# Atmega.net
KiCad netlist of a schematic drawn in Altium Designer
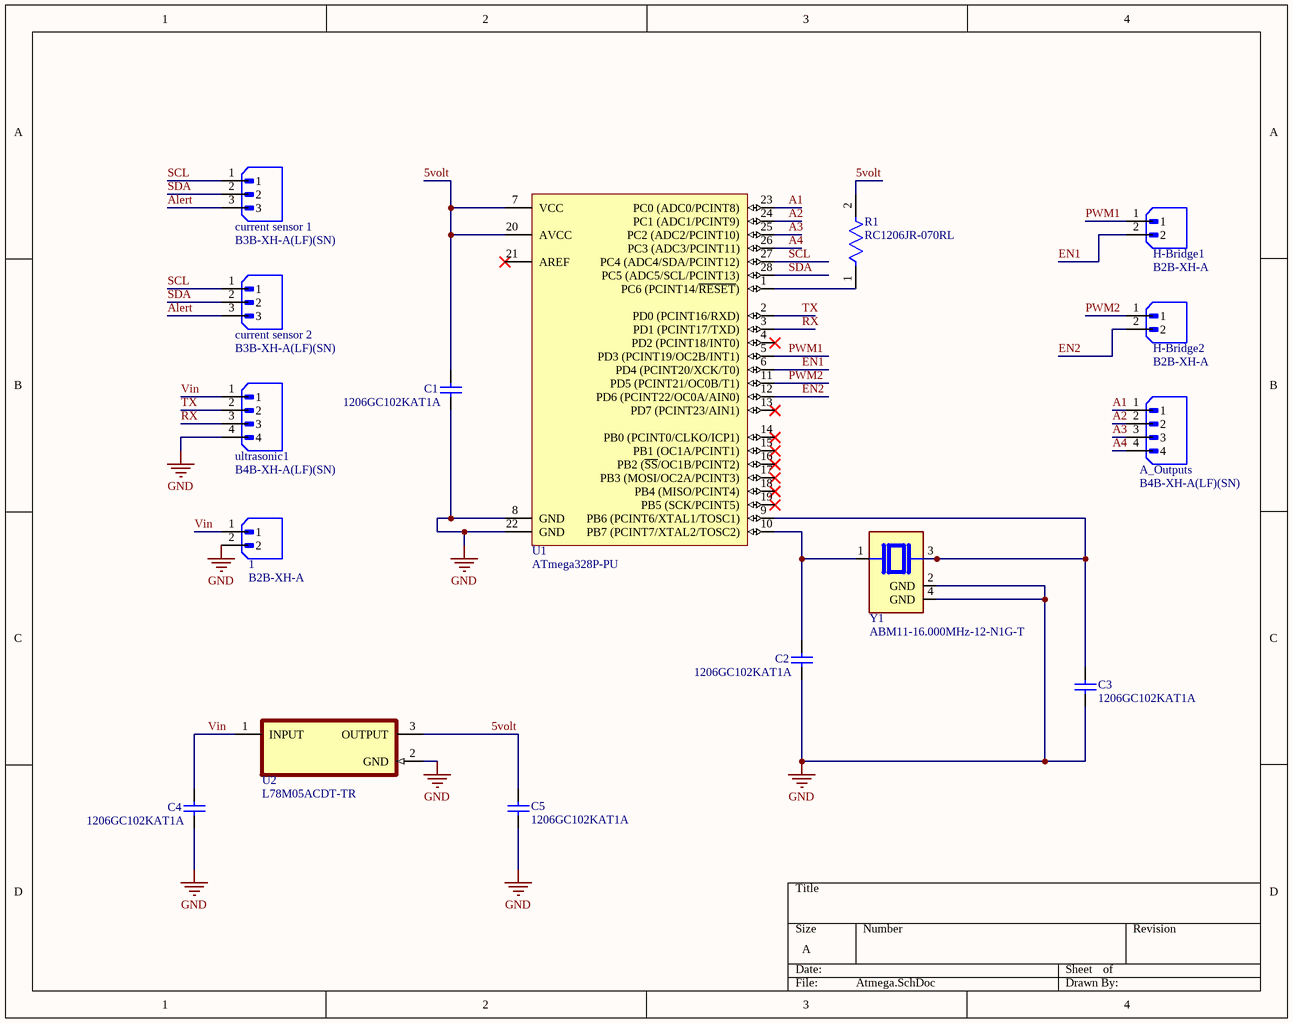
[diagram p0: Atmega.SchDoc]

(export (version "E")
  (design (tool "Eeschema 10.0.6"))
  (components
    (comp (ref "1")
      (value "B2B-XH-A")
      (footprint "JST_B2B-XH-A")
      (fields (field (name "MF") "{'manufacturer': u'JST Sales America Inc.'}"))
      (libsource (lib "B2B-XH-A") (part "B2B-XH-A"))
    )
    (comp (ref "A_Outputs")
      (value "B4B-XH-A(LF)(SN)")
      (footprint "JST_B4B-XH-A(LF)(SN)")
      (description "Connector Header Through Hole 4 position 0.098 (2.50mm)")
      (fields (field (name "MF") "JST Sales"))
      (libsource (lib "B4B-XH-A_LF__SN_") (part "B4B-XH-A(LF)(SN)"))
    )
    (comp (ref "C1")
      (value "1206GC102KAT1A")
      (footprint "AVX-1206-2_L")
      (description "Chip Capacitor, 1 nF, +/- 10%, -55 to 125 degC, 1206 (3216 Metric), RoHS, Tape and Reel")
      (fields (field (name "TOLERANCE") "10%") (field (name "MANUFACTURER") "AVX"))
      (libsource (lib "Altium Content Vault") (part "CAP-NP-2"))
    )
    (comp (ref "C2")
      (value "1206GC102KAT1A")
      (footprint "AVX-1206-2_L")
      (description "Chip Capacitor, 1 nF, +/- 10%, -55 to 125 degC, 1206 (3216 Metric), RoHS, Tape and Reel")
      (fields (field (name "TOLERANCE") "10%") (field (name "MANUFACTURER") "AVX"))
      (libsource (lib "Altium Content Vault") (part "CAP-NP-2"))
    )
    (comp (ref "C3")
      (value "1206GC102KAT1A")
      (footprint "AVX-1206-2_L")
      (description "Chip Capacitor, 1 nF, +/- 10%, -55 to 125 degC, 1206 (3216 Metric), RoHS, Tape and Reel")
      (fields (field (name "TOLERANCE") "10%") (field (name "MANUFACTURER") "AVX"))
      (libsource (lib "Altium Content Vault") (part "CAP-NP-2"))
    )
    (comp (ref "C4")
      (value "1206GC102KAT1A")
      (footprint "AVX-1206-2_L")
      (description "Chip Capacitor, 1 nF, +/- 10%, -55 to 125 degC, 1206 (3216 Metric), RoHS, Tape and Reel")
      (fields (field (name "TOLERANCE") "10%") (field (name "MANUFACTURER") "AVX"))
      (libsource (lib "Altium Content Vault") (part "CAP-NP-2"))
    )
    (comp (ref "C5")
      (value "1206GC102KAT1A")
      (footprint "AVX-1206-2_L")
      (description "Chip Capacitor, 1 nF, +/- 10%, -55 to 125 degC, 1206 (3216 Metric), RoHS, Tape and Reel")
      (fields (field (name "TOLERANCE") "10%") (field (name "MANUFACTURER") "AVX"))
      (libsource (lib "Altium Content Vault") (part "CAP-NP-2"))
    )
    (comp (ref "current sensor 1")
      (value "B3B-XH-A(LF)(SN)")
      (footprint "JST_B3B-XH-A(LF)(SN)")
      (description "Connector Header Through Hole 3 position 0.098 (2.50mm)")
      (fields (field (name "MF") "JST Sales"))
      (libsource (lib "B3B-XH-A_LF__SN_") (part "B3B-XH-A(LF)(SN)"))
    )
    (comp (ref "current sensor 2")
      (value "B3B-XH-A(LF)(SN)")
      (footprint "JST_B3B-XH-A(LF)(SN)")
      (description "Connector Header Through Hole 3 position 0.098 (2.50mm)")
      (fields (field (name "MF") "JST Sales"))
      (libsource (lib "B3B-XH-A_LF__SN_") (part "B3B-XH-A(LF)(SN)"))
    )
    (comp (ref "H-Bridge1")
      (value "B2B-XH-A")
      (footprint "JST_B2B-XH-A")
      (fields (field (name "MF") "{'manufacturer': u'JST Sales America Inc.'}"))
      (libsource (lib "B2B-XH-A") (part "B2B-XH-A"))
    )
    (comp (ref "H-Bridge2")
      (value "B2B-XH-A")
      (footprint "JST_B2B-XH-A")
      (fields (field (name "MF") "{'manufacturer': u'JST Sales America Inc.'}"))
      (libsource (lib "B2B-XH-A") (part "B2B-XH-A"))
    )
    (comp (ref "R1")
      (value "RC1206JR-070RL")
      (footprint "FP-RC1206-MFG")
      (description "RES SMD 0 OHM JUMPER 1/4W 1206")
      (fields
        (field (name "MANUFACTURER") "YAGEO")
        (field (name "OCTOPART") "https://octopart.com/rc1206jr-070rl-yageo-40025601")
      )
      (libsource (lib "Altium Content Vault") (part "1029c3af85768c4190bb7ad29bc67b5"))
    )
    (comp (ref "U1")
      (value "ATmega328P-PU")
      (footprint "28P3")
      (libsource (lib "Altium Content Vault") (part "MC-8B-ATM48-IL28"))
    )
    (comp (ref "U2")
      (value "L78M05ACDT-TR")
      (footprint "DPAK228P972X240-4N")
      (description "Linear Voltage Regulator IC 1 Output 500mA DPAK")
      (fields (field (name "MF") "STMicroelectronics"))
      (libsource (lib "L78M05ACDT-TR") (part "L78M05ACDT-TR"))
    )
    (comp (ref "ultrasonic1")
      (value "B4B-XH-A(LF)(SN)")
      (footprint "JST_B4B-XH-A(LF)(SN)")
      (description "Connector Header Through Hole 4 position 0.098 (2.50mm)")
      (fields (field (name "MF") "JST Sales"))
      (libsource (lib "B4B-XH-A_LF__SN_") (part "B4B-XH-A(LF)(SN)"))
    )
    (comp (ref "Y1")
      (value "ABM11-16.000MHz-12-N1G-T")
      (footprint "XTAL_ABM11-16.000MHz-12-N1G-T")
      (fields (field (name "MF") "{'manufacturer': u'Abracon LLC'}"))
      (libsource (lib "ABM11-16.000MHz-12-N1G-T") (part "ABM11-16.000MHz-12-N1G-T"))
    )
  )
  (nets
    (net (code "1") (name "/5volt") (class "Default")
      (node (ref "C1") (pin "2") (pinfunction "2_2") (pintype "passive"))
      (node (ref "C5") (pin "1") (pinfunction "1_1") (pintype "passive"))
      (node (ref "R1") (pin "2") (pinfunction "2_2") (pintype "passive"))
      (node (ref "U1") (pin "20") (pinfunction "AVCC_20") (pintype "power_in"))
      (node (ref "U1") (pin "7") (pinfunction "VCC_7") (pintype "power_in"))
      (node (ref "U2") (pin "3") (pinfunction "OUTPUT_3") (pintype "power_in"))
    )
    (net (code "2") (name "/A1") (class "Default")
      (node (ref "A_Outputs") (pin "1") (pinfunction "1_1") (pintype "passive"))
      (node (ref "U1") (pin "23") (pinfunction "PC0_(ADC0/PCINT8)_23") (pintype "bidirectional"))
    )
    (net (code "3") (name "/A2") (class "Default")
      (node (ref "A_Outputs") (pin "2") (pinfunction "2_2") (pintype "passive"))
      (node (ref "U1") (pin "24") (pinfunction "PC1_(ADC1/PCINT9)_24") (pintype "bidirectional"))
    )
    (net (code "4") (name "/A3") (class "Default")
      (node (ref "A_Outputs") (pin "3") (pinfunction "3_3") (pintype "passive"))
      (node (ref "U1") (pin "25") (pinfunction "PC2_(ADC2/PCINT10)_25") (pintype "bidirectional"))
    )
    (net (code "5") (name "/A4") (class "Default")
      (node (ref "A_Outputs") (pin "4") (pinfunction "4_4") (pintype "passive"))
      (node (ref "U1") (pin "26") (pinfunction "PC3_(ADC3/PCINT11)_26") (pintype "bidirectional"))
    )
    (net (code "6") (name "/Alert") (class "Default")
      (node (ref "current sensor 1") (pin "3") (pinfunction "3_3") (pintype "passive"))
      (node (ref "current sensor 2") (pin "3") (pinfunction "3_3") (pintype "passive"))
    )
    (net (code "7") (name "/EN1") (class "Default")
      (node (ref "H-Bridge1") (pin "2") (pinfunction "2_2") (pintype "passive"))
      (node (ref "U1") (pin "6") (pinfunction "PD4_(PCINT20/XCK/T0)_6") (pintype "bidirectional"))
    )
    (net (code "8") (name "/EN2") (class "Default")
      (node (ref "H-Bridge2") (pin "2") (pinfunction "2_2") (pintype "passive"))
      (node (ref "U1") (pin "12") (pinfunction "PD6_(PCINT22/OC0A/AIN0)_12") (pintype "bidirectional"))
    )
    (net (code "9") (name "/PWM1") (class "Default")
      (node (ref "H-Bridge1") (pin "1") (pinfunction "1_1") (pintype "passive"))
      (node (ref "U1") (pin "5") (pinfunction "PD3_(PCINT19/OC2B/INT1)_5") (pintype "bidirectional"))
    )
    (net (code "10") (name "/PWM2") (class "Default")
      (node (ref "H-Bridge2") (pin "1") (pinfunction "1_1") (pintype "passive"))
      (node (ref "U1") (pin "11") (pinfunction "PD5_(PCINT21/OC0B/T1)_11") (pintype "bidirectional"))
    )
    (net (code "11") (name "/RX") (class "Default")
      (node (ref "U1") (pin "3") (pinfunction "PD1_(PCINT17/TXD)_3") (pintype "bidirectional"))
      (node (ref "ultrasonic1") (pin "3") (pinfunction "3_3") (pintype "passive"))
    )
    (net (code "12") (name "/SCL") (class "Default")
      (node (ref "U1") (pin "27") (pinfunction "PC4_(ADC4/SDA/PCINT12)_27") (pintype "bidirectional"))
      (node (ref "current sensor 1") (pin "1") (pinfunction "1_1") (pintype "passive"))
      (node (ref "current sensor 2") (pin "1") (pinfunction "1_1") (pintype "passive"))
    )
    (net (code "13") (name "/SDA") (class "Default")
      (node (ref "U1") (pin "28") (pinfunction "PC5_(ADC5/SCL/PCINT13)_28") (pintype "bidirectional"))
      (node (ref "current sensor 1") (pin "2") (pinfunction "2_2") (pintype "passive"))
      (node (ref "current sensor 2") (pin "2") (pinfunction "2_2") (pintype "passive"))
    )
    (net (code "14") (name "/TX") (class "Default")
      (node (ref "U1") (pin "2") (pinfunction "PD0_(PCINT16/RXD)_2") (pintype "bidirectional"))
      (node (ref "ultrasonic1") (pin "2") (pinfunction "2_2") (pintype "passive"))
    )
    (net (code "15") (name "/Vin") (class "Default")
      (node (ref "1") (pin "1") (pinfunction "1_1") (pintype "passive"))
      (node (ref "C4") (pin "2") (pinfunction "2_2") (pintype "passive"))
      (node (ref "U2") (pin "1") (pinfunction "INPUT_1") (pintype "power_in"))
      (node (ref "ultrasonic1") (pin "1") (pinfunction "1_1") (pintype "passive"))
    )
    (net (code "16") (name "GND") (class "Default")
      (node (ref "1") (pin "2") (pinfunction "2_2") (pintype "passive"))
      (node (ref "C1") (pin "1") (pinfunction "1_1") (pintype "passive"))
      (node (ref "C2") (pin "1") (pinfunction "1_1") (pintype "passive"))
      (node (ref "C3") (pin "1") (pinfunction "1_1") (pintype "passive"))
      (node (ref "C4") (pin "1") (pinfunction "1_1") (pintype "passive"))
      (node (ref "C5") (pin "2") (pinfunction "2_2") (pintype "passive"))
      (node (ref "U1") (pin "22") (pinfunction "GND_22") (pintype "power_in"))
      (node (ref "U1") (pin "8") (pinfunction "GND_8") (pintype "power_in"))
      (node (ref "U2") (pin "2") (pinfunction "GND_2") (pintype "input"))
      (node (ref "Y1") (pin "2") (pinfunction "GND_2") (pintype "power_in"))
      (node (ref "Y1") (pin "4") (pinfunction "GND_4") (pintype "power_in"))
      (node (ref "ultrasonic1") (pin "4") (pinfunction "4_4") (pintype "passive"))
    )
    (net (code "17") (name "Net-(U1-PB6_(PCINT6{slash}XTAL1{slash}TOSC1))") (class "Default")
      (node (ref "C3") (pin "2") (pinfunction "2_2") (pintype "passive"))
      (node (ref "U1") (pin "9") (pinfunction "PB6_(PCINT6/XTAL1/TOSC1)_9") (pintype "bidirectional"))
      (node (ref "Y1") (pin "3") (pinfunction "2_3") (pintype "passive"))
    )
    (net (code "18") (name "Net-(U1-PB7_(PCINT7{slash}XTAL2{slash}TOSC2))") (class "Default")
      (node (ref "C2") (pin "2") (pinfunction "2_2") (pintype "passive"))
      (node (ref "U1") (pin "10") (pinfunction "PB7_(PCINT7/XTAL2/TOSC2)_10") (pintype "bidirectional"))
      (node (ref "Y1") (pin "1") (pinfunction "1_1") (pintype "passive"))
    )
    (net (code "19") (name "Net-(U1-PC6_(PCINT14{slash}~{RESET}))") (class "Default")
      (node (ref "R1") (pin "1") (pinfunction "1_1") (pintype "passive"))
      (node (ref "U1") (pin "1") (pinfunction "PC6_(PCINT14/~{RESET})_1") (pintype "bidirectional"))
    )
    (net (code "20") (name "unconnected-(U1-AREF-Pad21)") (class "Default")
      (node (ref "U1") (pin "21") (pinfunction "AREF_21") (pintype "power_in+no_connect"))
    )
    (net (code "21") (name "unconnected-(U1-PB0_(PCINT0{slash}CLKO{slash}ICP1)-Pad14)") (class "Default")
      (node (ref "U1") (pin "14") (pinfunction "PB0_(PCINT0/CLKO/ICP1)_14") (pintype "bidirectional+no_connect"))
    )
    (net (code "22") (name "unconnected-(U1-PB1_(OC1A{slash}PCINT1)-Pad15)") (class "Default")
      (node (ref "U1") (pin "15") (pinfunction "PB1_(OC1A/PCINT1)_15") (pintype "bidirectional+no_connect"))
    )
    (net (code "23") (name "unconnected-(U1-PB2_(~{SS}{slash}OC1B{slash}PCINT2)-Pad16)") (class "Default")
      (node (ref "U1") (pin "16") (pinfunction "PB2_(~{SS}/OC1B/PCINT2)_16") (pintype "bidirectional+no_connect"))
    )
    (net (code "24") (name "unconnected-(U1-PB3_(MOSI{slash}OC2A{slash}PCINT3)-Pad17)") (class "Default")
      (node (ref "U1") (pin "17") (pinfunction "PB3_(MOSI/OC2A/PCINT3)_17") (pintype "bidirectional+no_connect"))
    )
    (net (code "25") (name "unconnected-(U1-PB4_(MISO{slash}PCINT4)-Pad18)") (class "Default")
      (node (ref "U1") (pin "18") (pinfunction "PB4_(MISO/PCINT4)_18") (pintype "bidirectional+no_connect"))
    )
    (net (code "26") (name "unconnected-(U1-PB5_(SCK{slash}PCINT5)-Pad19)") (class "Default")
      (node (ref "U1") (pin "19") (pinfunction "PB5_(SCK/PCINT5)_19") (pintype "bidirectional+no_connect"))
    )
    (net (code "27") (name "unconnected-(U1-PD2_(PCINT18{slash}INT0)-Pad4)") (class "Default")
      (node (ref "U1") (pin "4") (pinfunction "PD2_(PCINT18/INT0)_4") (pintype "bidirectional+no_connect"))
    )
    (net (code "28") (name "unconnected-(U1-PD7_(PCINT23{slash}AIN1)-Pad13)") (class "Default")
      (node (ref "U1") (pin "13") (pinfunction "PD7_(PCINT23/AIN1)_13") (pintype "bidirectional+no_connect"))
    )
  )
)
